# BatteryCharger.net
KiCad netlist of a schematic drawn in Altium Designer
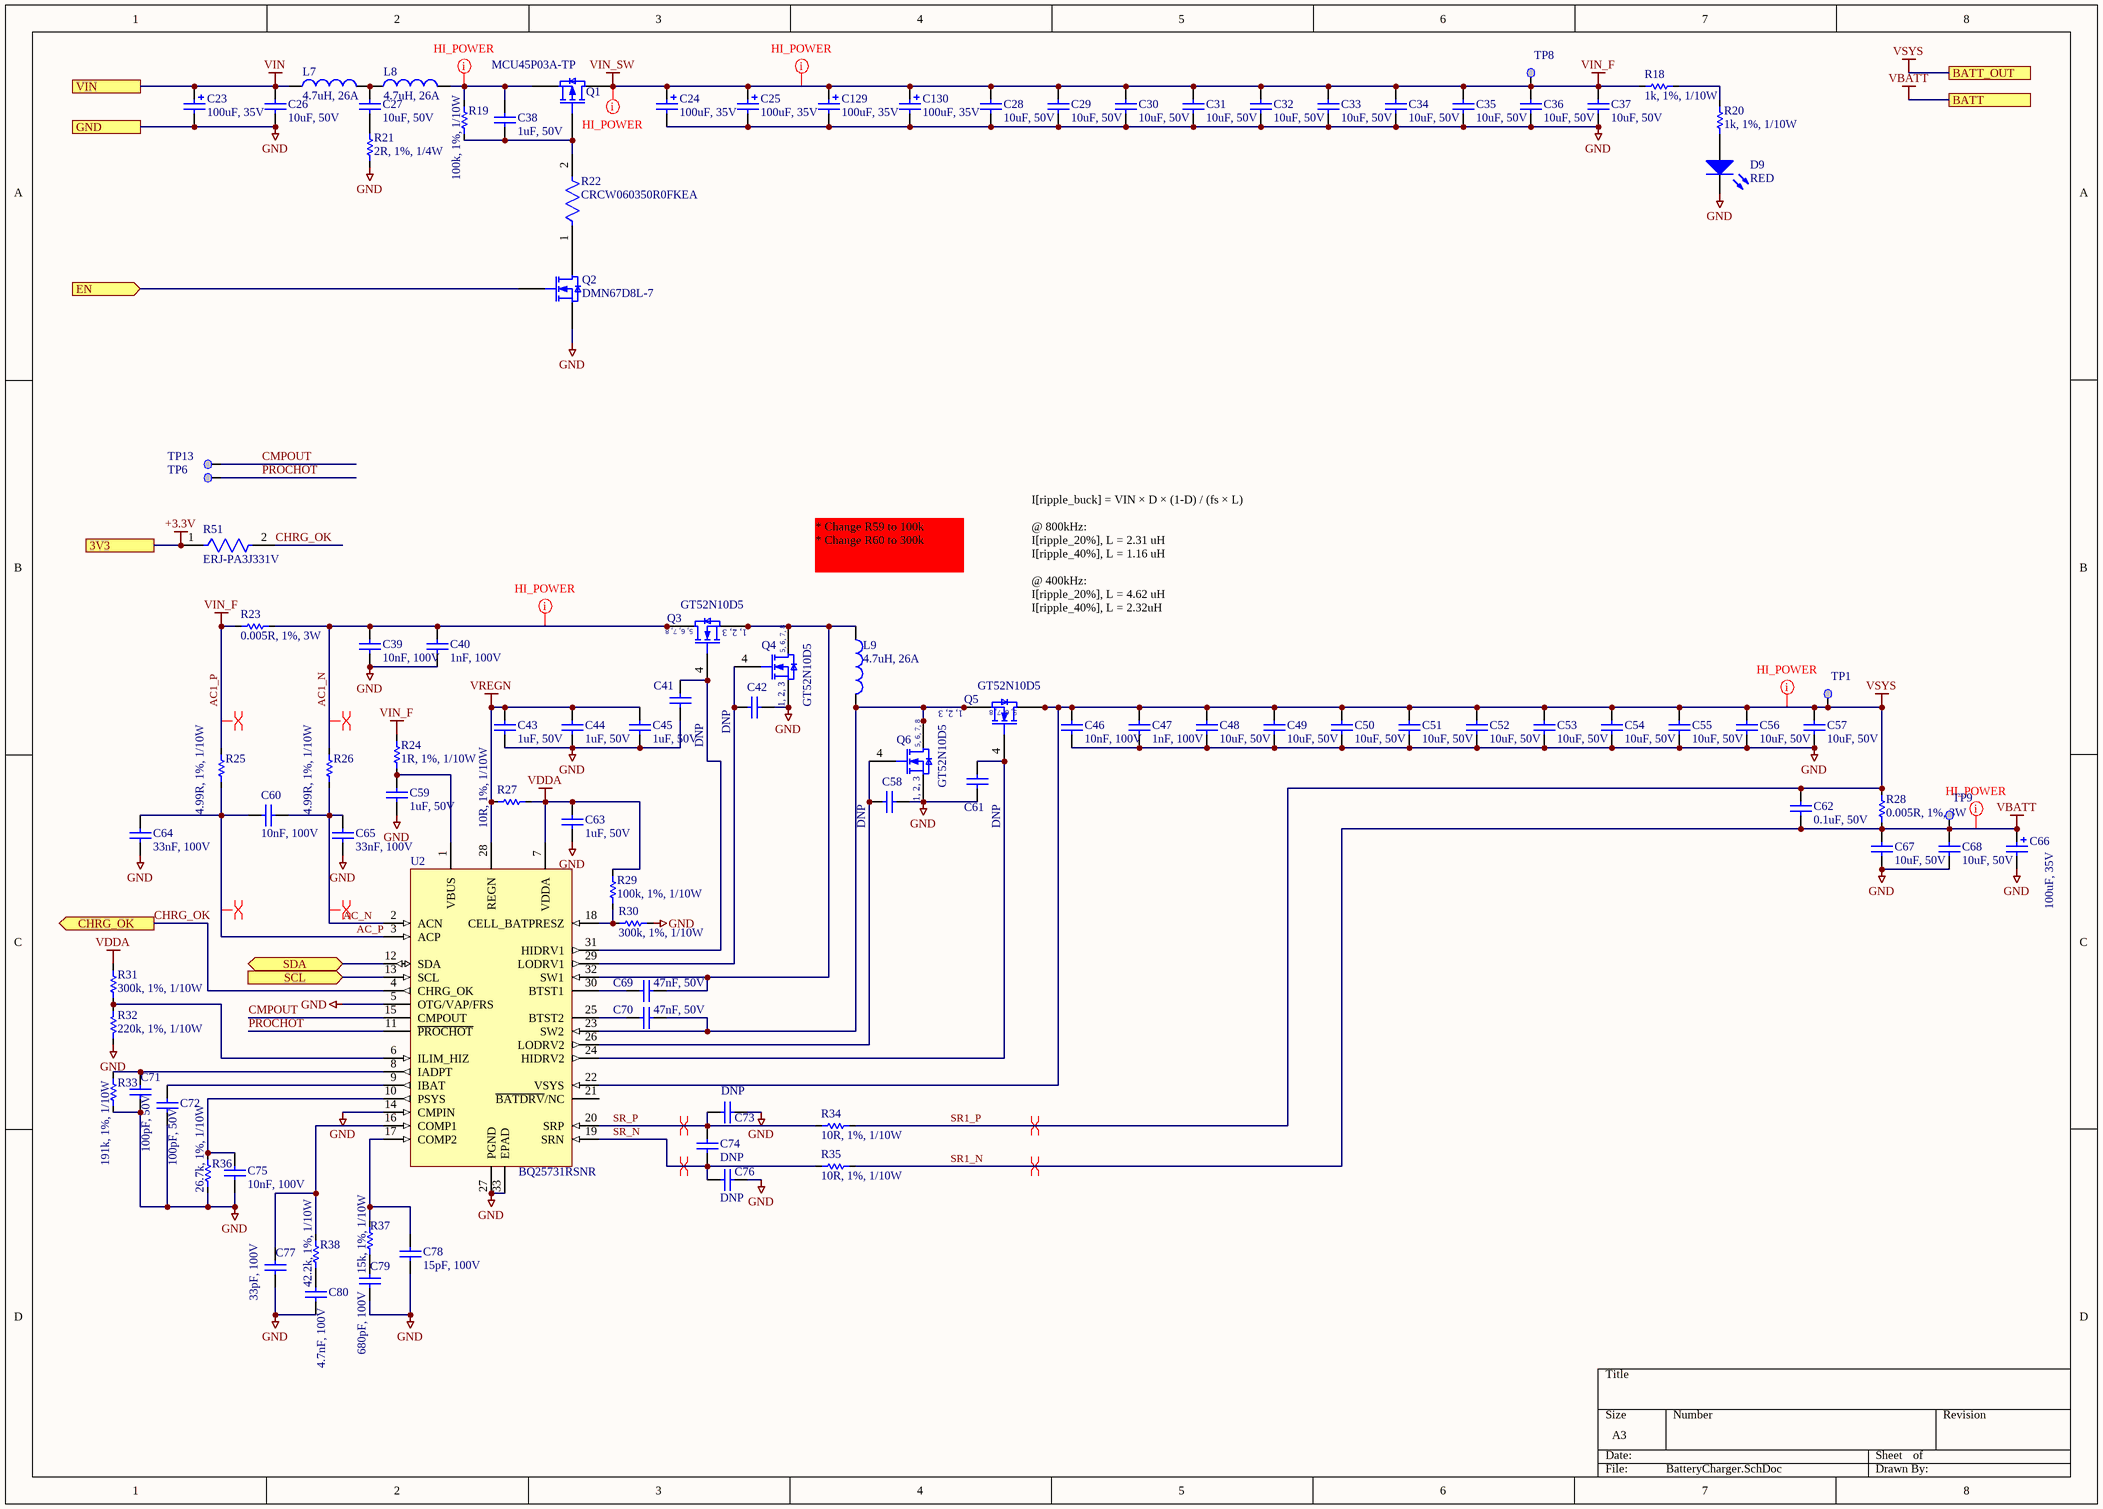
[diagram p0: BatteryCharger.SchDoc]

(export (version "E")
  (design (tool "Eeschema 10.0.6"))
  (components
    (comp (ref "C23")
      (value "100uF, 35V")
      (footprint "CAPAE7866X80L")
      (description "CAP ALUM 100UF 20% 35V SMD")
      (fields (field (name "PART NUMBER") "NS00911"))
      (libsource (lib "FullPartsDB") (part "CAP_POL"))
    )
    (comp (ref "C24")
      (value "100uF, 35V")
      (footprint "CAPAE7866X80L")
      (description "CAP ALUM 100UF 20% 35V SMD")
      (fields (field (name "PART NUMBER") "NS00911"))
      (libsource (lib "FullPartsDB") (part "CAP_POL"))
    )
    (comp (ref "C25")
      (value "100uF, 35V")
      (footprint "CAPAE7866X80L")
      (description "CAP ALUM 100UF 20% 35V SMD")
      (fields (field (name "PART NUMBER") "NS00911"))
      (libsource (lib "FullPartsDB") (part "CAP_POL"))
    )
    (comp (ref "C26")
      (value "10uF, 50V")
      (footprint "1206")
      (description "CAP CER 10UF 50V X7R 1206")
      (fields (field (name "PART NUMBER") "NS00832"))
      (libsource (lib "FullPartsDB") (part "Cap"))
    )
    (comp (ref "C27")
      (value "10uF, 50V")
      (footprint "1206")
      (description "CAP CER 10UF 50V X7R 1206")
      (fields (field (name "PART NUMBER") "NS00832"))
      (libsource (lib "FullPartsDB") (part "Cap"))
    )
    (comp (ref "C28")
      (value "10uF, 50V")
      (footprint "1206")
      (description "CAP CER 10UF 50V X7R 1206")
      (fields (field (name "PART NUMBER") "NS00832"))
      (libsource (lib "FullPartsDB") (part "Cap"))
    )
    (comp (ref "C29")
      (value "10uF, 50V")
      (footprint "1206")
      (description "CAP CER 10UF 50V X7R 1206")
      (fields (field (name "PART NUMBER") "NS00832"))
      (libsource (lib "FullPartsDB") (part "Cap"))
    )
    (comp (ref "C30")
      (value "10uF, 50V")
      (footprint "1206")
      (description "CAP CER 10UF 50V X7R 1206")
      (fields (field (name "PART NUMBER") "NS00832"))
      (libsource (lib "FullPartsDB") (part "Cap"))
    )
    (comp (ref "C31")
      (value "10uF, 50V")
      (footprint "1206")
      (description "CAP CER 10UF 50V X7R 1206")
      (fields (field (name "PART NUMBER") "NS00832"))
      (libsource (lib "FullPartsDB") (part "Cap"))
    )
    (comp (ref "C32")
      (value "10uF, 50V")
      (footprint "1206")
      (description "CAP CER 10UF 50V X7R 1206")
      (fields (field (name "PART NUMBER") "NS00832"))
      (libsource (lib "FullPartsDB") (part "Cap"))
    )
    (comp (ref "C33")
      (value "10uF, 50V")
      (footprint "1206")
      (description "CAP CER 10UF 50V X7R 1206")
      (fields (field (name "PART NUMBER") "NS00832"))
      (libsource (lib "FullPartsDB") (part "Cap"))
    )
    (comp (ref "C34")
      (value "10uF, 50V")
      (footprint "1206")
      (description "CAP CER 10UF 50V X7R 1206")
      (fields (field (name "PART NUMBER") "NS00832"))
      (libsource (lib "FullPartsDB") (part "Cap"))
    )
    (comp (ref "C35")
      (value "10uF, 50V")
      (footprint "1206")
      (description "CAP CER 10UF 50V X7R 1206")
      (fields (field (name "PART NUMBER") "NS00832"))
      (libsource (lib "FullPartsDB") (part "Cap"))
    )
    (comp (ref "C36")
      (value "10uF, 50V")
      (footprint "1206")
      (description "CAP CER 10UF 50V X7R 1206")
      (fields (field (name "PART NUMBER") "NS00832"))
      (libsource (lib "FullPartsDB") (part "Cap"))
    )
    (comp (ref "C37")
      (value "10uF, 50V")
      (footprint "1206")
      (description "CAP CER 10UF 50V X7R 1206")
      (fields (field (name "PART NUMBER") "NS00832"))
      (libsource (lib "FullPartsDB") (part "Cap"))
    )
    (comp (ref "C38")
      (value "1uF, 50V")
      (footprint "0805")
      (description "CAP CER 1UF 50V X7R 0805")
      (fields (field (name "PART NUMBER") "NS00871"))
      (libsource (lib "FullPartsDB") (part "Cap"))
    )
    (comp (ref "C39")
      (value "10nF, 100V")
      (footprint "0603")
      (description "CAP CER 10000PF 100V C0G 0603")
      (fields (field (name "PART NUMBER") "NS00848"))
      (libsource (lib "FullPartsDB") (part "Cap"))
    )
    (comp (ref "C40")
      (value "1nF, 100V")
      (footprint "0603")
      (description "CAP CER 1000PF 100V C0G/NP0 0603")
      (fields (field (name "PART NUMBER") "NS00847"))
      (libsource (lib "FullPartsDB") (part "Cap"))
    )
    (comp (ref "C41")
      (value "DNP")
      (footprint "0603")
      (description "CAP CER 100PF 50V C0G/NP0 0603")
      (fields (field (name "PART NUMBER") "NS00840"))
      (libsource (lib "FullPartsDB") (part "Cap"))
    )
    (comp (ref "C42")
      (value "DNP")
      (footprint "0603")
      (description "CAP CER 100PF 50V C0G/NP0 0603")
      (fields (field (name "PART NUMBER") "NS00840"))
      (libsource (lib "FullPartsDB") (part "Cap"))
    )
    (comp (ref "C43")
      (value "1uF, 50V")
      (footprint "0805")
      (description "CAP CER 1UF 50V X7R 0805")
      (fields (field (name "PART NUMBER") "NS00871"))
      (libsource (lib "FullPartsDB") (part "Cap"))
    )
    (comp (ref "C44")
      (value "1uF, 50V")
      (footprint "0805")
      (description "CAP CER 1UF 50V X7R 0805")
      (fields (field (name "PART NUMBER") "NS00871"))
      (libsource (lib "FullPartsDB") (part "Cap"))
    )
    (comp (ref "C45")
      (value "1uF, 50V")
      (footprint "0805")
      (description "CAP CER 1UF 50V X7R 0805")
      (fields (field (name "PART NUMBER") "NS00871"))
      (libsource (lib "FullPartsDB") (part "Cap"))
    )
    (comp (ref "C46")
      (value "10nF, 100V")
      (footprint "0603")
      (description "CAP CER 10000PF 100V C0G 0603")
      (fields (field (name "PART NUMBER") "NS00848"))
      (libsource (lib "FullPartsDB") (part "Cap"))
    )
    (comp (ref "C47")
      (value "1nF, 100V")
      (footprint "0603")
      (description "CAP CER 1000PF 100V C0G/NP0 0603")
      (fields (field (name "PART NUMBER") "NS00847"))
      (libsource (lib "FullPartsDB") (part "Cap"))
    )
    (comp (ref "C48")
      (value "10uF, 50V")
      (footprint "1206")
      (description "CAP CER 10UF 50V X7R 1206")
      (fields (field (name "PART NUMBER") "NS00832"))
      (libsource (lib "FullPartsDB") (part "Cap"))
    )
    (comp (ref "C49")
      (value "10uF, 50V")
      (footprint "1206")
      (description "CAP CER 10UF 50V X7R 1206")
      (fields (field (name "PART NUMBER") "NS00832"))
      (libsource (lib "FullPartsDB") (part "Cap"))
    )
    (comp (ref "C50")
      (value "10uF, 50V")
      (footprint "1206")
      (description "CAP CER 10UF 50V X7R 1206")
      (fields (field (name "PART NUMBER") "NS00832"))
      (libsource (lib "FullPartsDB") (part "Cap"))
    )
    (comp (ref "C51")
      (value "10uF, 50V")
      (footprint "1206")
      (description "CAP CER 10UF 50V X7R 1206")
      (fields (field (name "PART NUMBER") "NS00832"))
      (libsource (lib "FullPartsDB") (part "Cap"))
    )
    (comp (ref "C52")
      (value "10uF, 50V")
      (footprint "1206")
      (description "CAP CER 10UF 50V X7R 1206")
      (fields (field (name "PART NUMBER") "NS00832"))
      (libsource (lib "FullPartsDB") (part "Cap"))
    )
    (comp (ref "C53")
      (value "10uF, 50V")
      (footprint "1206")
      (description "CAP CER 10UF 50V X7R 1206")
      (fields (field (name "PART NUMBER") "NS00832"))
      (libsource (lib "FullPartsDB") (part "Cap"))
    )
    (comp (ref "C54")
      (value "10uF, 50V")
      (footprint "1206")
      (description "CAP CER 10UF 50V X7R 1206")
      (fields (field (name "PART NUMBER") "NS00832"))
      (libsource (lib "FullPartsDB") (part "Cap"))
    )
    (comp (ref "C55")
      (value "10uF, 50V")
      (footprint "1206")
      (description "CAP CER 10UF 50V X7R 1206")
      (fields (field (name "PART NUMBER") "NS00832"))
      (libsource (lib "FullPartsDB") (part "Cap"))
    )
    (comp (ref "C56")
      (value "10uF, 50V")
      (footprint "1206")
      (description "CAP CER 10UF 50V X7R 1206")
      (fields (field (name "PART NUMBER") "NS00832"))
      (libsource (lib "FullPartsDB") (part "Cap"))
    )
    (comp (ref "C57")
      (value "10uF, 50V")
      (footprint "1206")
      (description "CAP CER 10UF 50V X7R 1206")
      (fields (field (name "PART NUMBER") "NS00832"))
      (libsource (lib "FullPartsDB") (part "Cap"))
    )
    (comp (ref "C58")
      (value "DNP")
      (footprint "0603")
      (description "CAP CER 100PF 50V C0G/NP0 0603")
      (fields (field (name "PART NUMBER") "NS00840"))
      (libsource (lib "FullPartsDB") (part "Cap"))
    )
    (comp (ref "C59")
      (value "1uF, 50V")
      (footprint "0805")
      (description "CAP CER 1UF 50V X7R 0805")
      (fields (field (name "PART NUMBER") "NS00871"))
      (libsource (lib "FullPartsDB") (part "Cap"))
    )
    (comp (ref "C60")
      (value "10nF, 100V")
      (footprint "0603")
      (description "CAP CER 10000PF 100V C0G 0603")
      (fields (field (name "PART NUMBER") "NS00848"))
      (libsource (lib "FullPartsDB") (part "Cap"))
    )
    (comp (ref "C61")
      (value "DNP")
      (footprint "0603")
      (description "CAP CER 100PF 50V C0G/NP0 0603")
      (fields (field (name "PART NUMBER") "NS00840"))
      (libsource (lib "FullPartsDB") (part "Cap"))
    )
    (comp (ref "C62")
      (value "0.1uF, 50V")
      (footprint "0603")
      (description "CAP CER 0.1UF 50V X7R 0603")
      (fields (field (name "PART NUMBER") "NS00838"))
      (libsource (lib "FullPartsDB") (part "Cap"))
    )
    (comp (ref "C63")
      (value "1uF, 50V")
      (footprint "0805")
      (description "CAP CER 1UF 50V X7R 0805")
      (fields (field (name "PART NUMBER") "NS00871"))
      (libsource (lib "FullPartsDB") (part "Cap"))
    )
    (comp (ref "C64")
      (value "33nF, 100V")
      (footprint "0805_CAP")
      (description "CAP CER 0.033UF 100V C0G 0805")
      (fields (field (name "PART NUMBER") "NS00800"))
      (libsource (lib "FullPartsDB") (part "Cap"))
    )
    (comp (ref "C65")
      (value "33nF, 100V")
      (footprint "0805_CAP")
      (description "CAP CER 0.033UF 100V C0G 0805")
      (fields (field (name "PART NUMBER") "NS00800"))
      (libsource (lib "FullPartsDB") (part "Cap"))
    )
    (comp (ref "C66")
      (value "100uF, 35V")
      (footprint "CAPAE7866X80L")
      (description "CAP ALUM 100UF 20% 35V SMD")
      (fields (field (name "PART NUMBER") "NS00911"))
      (libsource (lib "FullPartsDB") (part "CAP_POL"))
    )
    (comp (ref "C67")
      (value "10uF, 50V")
      (footprint "1206")
      (description "CAP CER 10UF 50V X7R 1206")
      (fields (field (name "PART NUMBER") "NS00832"))
      (libsource (lib "FullPartsDB") (part "Cap"))
    )
    (comp (ref "C68")
      (value "10uF, 50V")
      (footprint "1206")
      (description "CAP CER 10UF 50V X7R 1206")
      (fields (field (name "PART NUMBER") "NS00832"))
      (libsource (lib "FullPartsDB") (part "Cap"))
    )
    (comp (ref "C69")
      (value "47nF, 50V")
      (footprint "0603")
      (description "CAP CER 0.047UF 50V X7R 0603")
      (fields (field (name "PART NUMBER") "NS00804"))
      (libsource (lib "FullPartsDB") (part "Cap"))
    )
    (comp (ref "C70")
      (value "47nF, 50V")
      (footprint "0603")
      (description "CAP CER 0.047UF 50V X7R 0603")
      (fields (field (name "PART NUMBER") "NS00804"))
      (libsource (lib "FullPartsDB") (part "Cap"))
    )
    (comp (ref "C71")
      (value "100pF, 50V")
      (footprint "0603")
      (description "CAP CER 100PF 50V C0G/NP0 0603")
      (fields (field (name "PART NUMBER") "NS00840"))
      (libsource (lib "FullPartsDB") (part "Cap"))
    )
    (comp (ref "C72")
      (value "100pF, 50V")
      (footprint "0603")
      (description "CAP CER 100PF 50V C0G/NP0 0603")
      (fields (field (name "PART NUMBER") "NS00840"))
      (libsource (lib "FullPartsDB") (part "Cap"))
    )
    (comp (ref "C73")
      (value "DNP")
      (footprint "0603")
      (description "CAP CER 0.068UF 50V X7R 0603")
      (fields (field (name "PART NUMBER") "NS00895"))
      (libsource (lib "FullPartsDB") (part "Cap"))
    )
    (comp (ref "C74")
      (value "DNP")
      (footprint "0603")
      (description "CAP CER 0.068UF 50V X7R 0603")
      (fields (field (name "PART NUMBER") "NS00895"))
      (libsource (lib "FullPartsDB") (part "Cap"))
    )
    (comp (ref "C75")
      (value "10nF, 100V")
      (footprint "0603")
      (description "CAP CER 10000PF 100V C0G 0603")
      (fields (field (name "PART NUMBER") "NS00848"))
      (libsource (lib "FullPartsDB") (part "Cap"))
    )
    (comp (ref "C76")
      (value "DNP")
      (footprint "0603")
      (description "CAP CER 0.068UF 50V X7R 0603")
      (fields (field (name "PART NUMBER") "NS00895"))
      (libsource (lib "FullPartsDB") (part "Cap"))
    )
    (comp (ref "C77")
      (value "33pF, 100V")
      (footprint "0603")
      (description "CAP CER 33PF 100V C0G/NP0 0603")
      (fields (field (name "PART NUMBER") "NS00931"))
      (libsource (lib "FullPartsDB") (part "Cap"))
    )
    (comp (ref "C78")
      (value "15pF, 100V")
      (footprint "0603")
      (description "CAP CER 15PF 100V C0G/NP0 0603")
      (fields (field (name "PART NUMBER") "NS00932"))
      (libsource (lib "FullPartsDB") (part "Cap"))
    )
    (comp (ref "C79")
      (value "680pF, 100V")
      (footprint "0603")
      (description "CAP CER 680PF 100V C0G 0603")
      (fields (field (name "PART NUMBER") "NS00933"))
      (libsource (lib "FullPartsDB") (part "Cap"))
    )
    (comp (ref "C80")
      (value "4.7nF, 100V")
      (footprint "0603")
      (description "CAP CER 4700PF 100V C0G 0603")
      (fields (field (name "PART NUMBER") "NS00930"))
      (libsource (lib "FullPartsDB") (part "Cap"))
    )
    (comp (ref "C129")
      (value "100uF, 35V")
      (footprint "CAPAE7866X80L")
      (description "CAP ALUM 100UF 20% 35V SMD")
      (fields (field (name "PART NUMBER") "NS00911"))
      (libsource (lib "FullPartsDB") (part "CAP_POL"))
    )
    (comp (ref "C130")
      (value "100uF, 35V")
      (footprint "CAPAE7866X80L")
      (description "CAP ALUM 100UF 20% 35V SMD")
      (fields (field (name "PART NUMBER") "NS00911"))
      (libsource (lib "FullPartsDB") (part "CAP_POL"))
    )
    (comp (ref "D9")
      (value "RED")
      (footprint "0603_DIODE_K1A2")
      (description "LED RED CLEAR 1608 SMD")
      (fields (field (name "PART NUMBER") "NS00945"))
      (libsource (lib "FullPartsDB") (part "LED_K1A2"))
    )
    (comp (ref "L7")
      (value "4.7uH, 26A")
      (footprint "INDM178169X70N")
      (description "FIXED IND 4.7UH 26A 5.5 MOHM SMD")
      (fields (field (name "PART NUMBER") "NS00854"))
      (libsource (lib "FullPartsDB") (part "Inductor"))
    )
    (comp (ref "L8")
      (value "4.7uH, 26A")
      (footprint "INDM178169X70N")
      (description "FIXED IND 4.7UH 26A 5.5 MOHM SMD")
      (fields (field (name "PART NUMBER") "NS00854"))
      (libsource (lib "FullPartsDB") (part "Inductor"))
    )
    (comp (ref "L9")
      (value "4.7uH, 26A")
      (footprint "INDM178169X70N")
      (description "FIXED IND 4.7UH 26A 5.5 MOHM SMD")
      (fields (field (name "PART NUMBER") "NS00854"))
      (libsource (lib "FullPartsDB") (part "Inductor"))
    )
    (comp (ref "Q1")
      (value "MCU45P03A-TP")
      (footprint "DPAK")
      (description "P-CHANNEL MOSFET, DPAK")
      (fields (field (name "PART NUMBER") "NS00810"))
      (libsource (lib "FullPartsDB") (part "FET_P_GDS"))
    )
    (comp (ref "Q2")
      (value "DMN67D8L-7")
      (footprint "SOT23-3")
      (description "MOSFET N-CH 60V 210MA SOT23")
      (fields (field (name "PART NUMBER") "NS00873") (field (name "PUBLISHER") "Altium Limited"))
      (libsource (lib "FullPartsDB") (part "FET_N_GSD"))
    )
    (comp (ref "Q3")
      (value "GT52N10D5")
      (footprint "8-PowerSMD")
      (description "N-CH MOSFET 100V 71A 8-PowerTDFN")
      (fields (field (name "PART NUMBER") "NS00856") (field (name "PUBLISHER") "Altium Limited"))
      (libsource (lib "FullPartsDB") (part "FET_N_1G3S4D"))
    )
    (comp (ref "Q4")
      (value "GT52N10D5")
      (footprint "8-PowerSMD")
      (description "N-CH MOSFET 100V 71A 8-PowerTDFN")
      (fields (field (name "PART NUMBER") "NS00856") (field (name "PUBLISHER") "Altium Limited"))
      (libsource (lib "FullPartsDB") (part "FET_N_1G3S4D"))
    )
    (comp (ref "Q5")
      (value "GT52N10D5")
      (footprint "8-PowerSMD")
      (description "N-CH MOSFET 100V 71A 8-PowerTDFN")
      (fields (field (name "PART NUMBER") "NS00856") (field (name "PUBLISHER") "Altium Limited"))
      (libsource (lib "FullPartsDB") (part "FET_N_1G3S4D"))
    )
    (comp (ref "Q6")
      (value "GT52N10D5")
      (footprint "8-PowerSMD")
      (description "N-CH MOSFET 100V 71A 8-PowerTDFN")
      (fields (field (name "PART NUMBER") "NS00856") (field (name "PUBLISHER") "Altium Limited"))
      (libsource (lib "FullPartsDB") (part "FET_N_1G3S4D"))
    )
    (comp (ref "R18")
      (value "1k, 1%, 1/10W")
      (footprint "0603")
      (description "RES 1K OHM 1% 1/10W 0603")
      (fields (field (name "PART NUMBER") "NS00882"))
      (libsource (lib "FullPartsDB") (part "RESISTOR"))
    )
    (comp (ref "R19")
      (value "100k, 1%, 1/10W")
      (footprint "0603")
      (description "RES 100K OHM 1% 1/10W 0603")
      (fields (field (name "PART NUMBER") "NS00835"))
      (libsource (lib "FullPartsDB") (part "RESISTOR"))
    )
    (comp (ref "R20")
      (value "1k, 1%, 1/10W")
      (footprint "0603")
      (description "RES 1K OHM 1% 1/10W 0603")
      (fields (field (name "PART NUMBER") "NS00882"))
      (libsource (lib "FullPartsDB") (part "RESISTOR"))
    )
    (comp (ref "R21")
      (value "2R, 1%, 1/4W")
      (footprint "1206")
      (description "RES 2 OHM 1% 1/4W 1206")
      (fields (field (name "PART NUMBER") "NS00946"))
      (libsource (lib "FullPartsDB") (part "RESISTOR"))
    )
    (comp (ref "R22")
      (value "CRCW060350R0FKEA")
      (footprint "FP-CRCW0603-e3-IPC_A")
      (description "RES Thick Film, 50Ω, 1%, 0.1W, 100ppm/°C, 0603")
      (fields (field (name "TOLERANCE") "1%"))
      (libsource (lib "Altium Content Vault") (part "1029c3af85768c4190bb7ad29bc67b5"))
    )
    (comp (ref "R23")
      (value "0.005R, 1%, 3W")
      (footprint "2512_RES_1")
      (description "RES 0.005 OHM 1% 3W 2512")
      (fields (field (name "PART NUMBER") "NS00798"))
      (libsource (lib "FullPartsDB") (part "RESISTOR"))
    )
    (comp (ref "R24")
      (value "1R, 1%, 1/10W")
      (footprint "0603")
      (description "RES 1 OHM 1% 1/10W 0603")
      (fields (field (name "PART NUMBER") "NS00811"))
      (libsource (lib "FullPartsDB") (part "RESISTOR"))
    )
    (comp (ref "R25")
      (value "4.99R, 1%, 1/10W")
      (footprint "0603")
      (description "RES 4.99 OHM 1% 1/10W 0603")
      (fields (field (name "PART NUMBER") "NS00799"))
      (libsource (lib "FullPartsDB") (part "RESISTOR"))
    )
    (comp (ref "R26")
      (value "4.99R, 1%, 1/10W")
      (footprint "0603")
      (description "RES 4.99 OHM 1% 1/10W 0603")
      (fields (field (name "PART NUMBER") "NS00799"))
      (libsource (lib "FullPartsDB") (part "RESISTOR"))
    )
    (comp (ref "R27")
      (value "10R, 1%, 1/10W")
      (footprint "0603")
      (description "RES 10 OHM 1% 1/10W 0603")
      (fields (field (name "PART NUMBER") "NS00796"))
      (libsource (lib "FullPartsDB") (part "RESISTOR"))
    )
    (comp (ref "R28")
      (value "0.005R, 1%, 3W")
      (footprint "2512_RES_1")
      (description "RES 0.005 OHM 1% 3W 2512")
      (fields (field (name "PART NUMBER") "NS00798"))
      (libsource (lib "FullPartsDB") (part "RESISTOR"))
    )
    (comp (ref "R29")
      (value "100k, 1%, 1/10W")
      (footprint "0603")
      (description "RES 100K OHM 1% 1/10W 0603")
      (fields (field (name "PART NUMBER") "NS00835"))
      (libsource (lib "FullPartsDB") (part "RESISTOR"))
    )
    (comp (ref "R30")
      (value "300k, 1%, 1/10W")
      (footprint "0603")
      (description "RES 300K OHM 1% 1/10W 0603")
      (fields (field (name "PART NUMBER") "NS00837"))
      (libsource (lib "FullPartsDB") (part "RESISTOR"))
    )
    (comp (ref "R31")
      (value "300k, 1%, 1/10W")
      (footprint "0603")
      (description "RES 300K OHM 1% 1/10W 0603")
      (fields (field (name "PART NUMBER") "NS00837"))
      (libsource (lib "FullPartsDB") (part "RESISTOR"))
    )
    (comp (ref "R32")
      (value "220k, 1%, 1/10W")
      (footprint "0603")
      (description "RES SMD 220K OHM 1% 1/10W 0603")
      (fields (field (name "PART NUMBER") "NS00915"))
      (libsource (lib "FullPartsDB") (part "RESISTOR"))
    )
    (comp (ref "R33")
      (value "191k, 1%, 1/10W")
      (footprint "0603")
      (description "RES 191K OHM 1% 1/10W 0603")
      (fields (field (name "PART NUMBER") "NS00821"))
      (libsource (lib "FullPartsDB") (part "RESISTOR"))
    )
    (comp (ref "R34")
      (value "10R, 1%, 1/10W")
      (footprint "0603")
      (description "RES 10 OHM 1% 1/10W 0603")
      (fields (field (name "PART NUMBER") "NS00796"))
      (libsource (lib "FullPartsDB") (part "RESISTOR"))
    )
    (comp (ref "R35")
      (value "10R, 1%, 1/10W")
      (footprint "0603")
      (description "RES 10 OHM 1% 1/10W 0603")
      (fields (field (name "PART NUMBER") "NS00796"))
      (libsource (lib "FullPartsDB") (part "RESISTOR"))
    )
    (comp (ref "R36")
      (value "26.7k, 1%, 1/10W")
      (footprint "0603")
      (description "RES 26.7K OHM 1% 1/10W 0603")
      (fields (field (name "PART NUMBER") "NS00823"))
      (libsource (lib "FullPartsDB") (part "RESISTOR"))
    )
    (comp (ref "R37")
      (value "15k, 1%, 1/10W")
      (footprint "0603")
      (description "RES 15K OHM 1% 1/10W 0603")
      (fields (field (name "PART NUMBER") "NS00834"))
      (libsource (lib "FullPartsDB") (part "RESISTOR"))
    )
    (comp (ref "R38")
      (value "42.2k, 1%, 1/10W")
      (footprint "0603")
      (description "RES 42.2K OHM 1% 1/10W 0603")
      (fields (field (name "PART NUMBER") "NS00822"))
      (libsource (lib "FullPartsDB") (part "RESISTOR"))
    )
    (comp (ref "R51")
      (value "ERJ-PA3J331V")
      (footprint "FP-ERJPA3-MFG")
      (description "RES SMD 330 OHM 5% 1/4W 0603")
      (fields (field (name "TOLERANCE") "5%"))
      (libsource (lib "Altium Content Vault") (part "1029c3af85768c4190bb7ad29bc67b5"))
    )
    (comp (ref "TP1")
      (value "Test Point")
      (footprint "TEST POINT 40 Mil")
      (description "Test Point 0.3mm")
      (libsource (lib "1_EverythingElse") (part "Test Point"))
    )
    (comp (ref "TP6")
      (value "Test Point")
      (footprint "TEST POINT 40 Mil")
      (description "Test Point 0.3mm")
      (libsource (lib "") (part "Test Point_1"))
    )
    (comp (ref "TP8")
      (value "Test Point")
      (footprint "TEST POINT 40 Mil")
      (description "Test Point 0.3mm")
      (libsource (lib "1_EverythingElse") (part "Test Point"))
    )
    (comp (ref "TP9")
      (value "Test Point")
      (footprint "TEST POINT 40 Mil")
      (description "Test Point 0.3mm")
      (libsource (lib "1_EverythingElse") (part "Test Point"))
    )
    (comp (ref "TP13")
      (value "Test Point")
      (footprint "TEST POINT 40 Mil")
      (description "Test Point 0.3mm")
      (libsource (lib "") (part "Test Point_1"))
    )
    (comp (ref "U2")
      (value "BQ25731RSNR")
      (footprint "QFN40P400X400X80_HS-33L")
      (description "I2C 1-5 CELL NVDC BUCK-BOOST BAT")
      (fields (field (name "PART NUMBER") "NS00795"))
      (libsource (lib "FullPartsDB") (part "TI_BQ257[2.3]X"))
    )
  )
  (nets
    (net (code "1") (name "+3.3V") (class "Default")
      (node (ref "R51") (pin "1") (pinfunction "1_1") (pintype "passive"))
    )
    (net (code "2") (name "/AC1_N") (class "Default")
      (node (ref "C39") (pin "2") (pinfunction "2_2") (pintype "passive"))
      (node (ref "C40") (pin "2") (pinfunction "2_2") (pintype "passive"))
      (node (ref "Q3") (pin "5") (pinfunction "D1_5") (pintype "passive"))
      (node (ref "Q3") (pin "6") (pinfunction "D2_6") (pintype "passive"))
      (node (ref "Q3") (pin "7") (pinfunction "D3_7") (pintype "passive"))
      (node (ref "Q3") (pin "8") (pinfunction "D4_8") (pintype "passive"))
      (node (ref "R23") (pin "2") (pinfunction "2_2") (pintype "passive"))
      (node (ref "R26") (pin "2") (pinfunction "2_2") (pintype "passive"))
    )
    (net (code "3") (name "/AC_N") (class "Default")
      (node (ref "C60") (pin "1") (pinfunction "1_1") (pintype "passive"))
      (node (ref "C65") (pin "2") (pinfunction "2_2") (pintype "passive"))
      (node (ref "R26") (pin "1") (pinfunction "1_1") (pintype "passive"))
      (node (ref "U2") (pin "2") (pinfunction "ACN_2") (pintype "input"))
    )
    (net (code "4") (name "/AC_P") (class "Default")
      (node (ref "C60") (pin "2") (pinfunction "2_2") (pintype "passive"))
      (node (ref "C64") (pin "2") (pinfunction "2_2") (pintype "passive"))
      (node (ref "R25") (pin "1") (pinfunction "1_1") (pintype "passive"))
      (node (ref "U2") (pin "3") (pinfunction "ACP_3") (pintype "input"))
    )
    (net (code "5") (name "/CHRG_OK") (class "Default")
      (node (ref "R51") (pin "2") (pinfunction "2_2") (pintype "passive"))
      (node (ref "U2") (pin "4") (pinfunction "CHRG_OK_4") (pintype "output"))
    )
    (net (code "6") (name "/CMPOUT") (class "Default")
      (node (ref "TP13") (pin "1") (pinfunction "1_1") (pintype "passive"))
      (node (ref "U2") (pin "15") (pinfunction "CMPOUT_15") (pintype "open_collector"))
    )
    (net (code "7") (name "/EN") (class "Default")
      (node (ref "Q2") (pin "1") (pinfunction "G_1") (pintype "passive"))
    )
    (net (code "8") (name "/PROCHOT") (class "Default")
      (node (ref "TP6") (pin "1") (pinfunction "1_1") (pintype "passive"))
      (node (ref "U2") (pin "11") (pinfunction "PROCHOT_11") (pintype "open_collector"))
    )
    (net (code "9") (name "/SCL") (class "Default")
      (node (ref "U2") (pin "13") (pinfunction "SCL_13") (pintype "input"))
    )
    (net (code "10") (name "/SDA") (class "Default")
      (node (ref "U2") (pin "12") (pinfunction "SDA_12") (pintype "bidirectional"))
    )
    (net (code "11") (name "/SR_N") (class "Default")
      (node (ref "C74") (pin "1") (pinfunction "1_1") (pintype "passive"))
      (node (ref "C76") (pin "1") (pinfunction "1_1") (pintype "passive"))
      (node (ref "R35") (pin "1") (pinfunction "1_1") (pintype "passive"))
      (node (ref "U2") (pin "19") (pinfunction "SRN_19") (pintype "input"))
    )
    (net (code "12") (name "/SR_P") (class "Default")
      (node (ref "C73") (pin "1") (pinfunction "1_1") (pintype "passive"))
      (node (ref "C74") (pin "2") (pinfunction "2_2") (pintype "passive"))
      (node (ref "R34") (pin "1") (pinfunction "1_1") (pintype "passive"))
      (node (ref "U2") (pin "20") (pinfunction "SRP_20") (pintype "input"))
    )
    (net (code "13") (name "GND") (class "Default")
      (node (ref "C129") (pin "2") (pinfunction "2_2") (pintype "passive"))
      (node (ref "C130") (pin "2") (pinfunction "2_2") (pintype "passive"))
      (node (ref "C23") (pin "2") (pinfunction "2_2") (pintype "passive"))
      (node (ref "C24") (pin "2") (pinfunction "2_2") (pintype "passive"))
      (node (ref "C25") (pin "2") (pinfunction "2_2") (pintype "passive"))
      (node (ref "C26") (pin "1") (pinfunction "1_1") (pintype "passive"))
      (node (ref "C28") (pin "1") (pinfunction "1_1") (pintype "passive"))
      (node (ref "C29") (pin "1") (pinfunction "1_1") (pintype "passive"))
      (node (ref "C30") (pin "1") (pinfunction "1_1") (pintype "passive"))
      (node (ref "C31") (pin "1") (pinfunction "1_1") (pintype "passive"))
      (node (ref "C32") (pin "1") (pinfunction "1_1") (pintype "passive"))
      (node (ref "C33") (pin "1") (pinfunction "1_1") (pintype "passive"))
      (node (ref "C34") (pin "1") (pinfunction "1_1") (pintype "passive"))
      (node (ref "C35") (pin "1") (pinfunction "1_1") (pintype "passive"))
      (node (ref "C36") (pin "1") (pinfunction "1_1") (pintype "passive"))
      (node (ref "C37") (pin "1") (pinfunction "1_1") (pintype "passive"))
      (node (ref "C39") (pin "1") (pinfunction "1_1") (pintype "passive"))
      (node (ref "C40") (pin "1") (pinfunction "1_1") (pintype "passive"))
      (node (ref "C41") (pin "2") (pinfunction "2_2") (pintype "passive"))
      (node (ref "C42") (pin "2") (pinfunction "2_2") (pintype "passive"))
      (node (ref "C43") (pin "1") (pinfunction "1_1") (pintype "passive"))
      (node (ref "C44") (pin "1") (pinfunction "1_1") (pintype "passive"))
      (node (ref "C45") (pin "1") (pinfunction "1_1") (pintype "passive"))
      (node (ref "C46") (pin "1") (pinfunction "1_1") (pintype "passive"))
      (node (ref "C47") (pin "1") (pinfunction "1_1") (pintype "passive"))
      (node (ref "C48") (pin "1") (pinfunction "1_1") (pintype "passive"))
      (node (ref "C49") (pin "1") (pinfunction "1_1") (pintype "passive"))
      (node (ref "C50") (pin "1") (pinfunction "1_1") (pintype "passive"))
      (node (ref "C51") (pin "1") (pinfunction "1_1") (pintype "passive"))
      (node (ref "C52") (pin "1") (pinfunction "1_1") (pintype "passive"))
      (node (ref "C53") (pin "1") (pinfunction "1_1") (pintype "passive"))
      (node (ref "C54") (pin "1") (pinfunction "1_1") (pintype "passive"))
      (node (ref "C55") (pin "1") (pinfunction "1_1") (pintype "passive"))
      (node (ref "C56") (pin "1") (pinfunction "1_1") (pintype "passive"))
      (node (ref "C57") (pin "1") (pinfunction "1_1") (pintype "passive"))
      (node (ref "C58") (pin "2") (pinfunction "2_2") (pintype "passive"))
      (node (ref "C59") (pin "1") (pinfunction "1_1") (pintype "passive"))
      (node (ref "C61") (pin "2") (pinfunction "2_2") (pintype "passive"))
      (node (ref "C63") (pin "1") (pinfunction "1_1") (pintype "passive"))
      (node (ref "C64") (pin "1") (pinfunction "1_1") (pintype "passive"))
      (node (ref "C65") (pin "1") (pinfunction "1_1") (pintype "passive"))
      (node (ref "C66") (pin "2") (pinfunction "2_2") (pintype "passive"))
      (node (ref "C67") (pin "1") (pinfunction "1_1") (pintype "passive"))
      (node (ref "C68") (pin "1") (pinfunction "1_1") (pintype "passive"))
      (node (ref "C71") (pin "2") (pinfunction "2_2") (pintype "passive"))
      (node (ref "C72") (pin "1") (pinfunction "1_1") (pintype "passive"))
      (node (ref "C73") (pin "2") (pinfunction "2_2") (pintype "passive"))
      (node (ref "C75") (pin "1") (pinfunction "1_1") (pintype "passive"))
      (node (ref "C76") (pin "2") (pinfunction "2_2") (pintype "passive"))
      (node (ref "C77") (pin "1") (pinfunction "1_1") (pintype "passive"))
      (node (ref "C78") (pin "1") (pinfunction "1_1") (pintype "passive"))
      (node (ref "C79") (pin "1") (pinfunction "1_1") (pintype "passive"))
      (node (ref "C80") (pin "1") (pinfunction "1_1") (pintype "passive"))
      (node (ref "D9") (pin "2") (pinfunction "K_2") (pintype "passive"))
      (node (ref "Q2") (pin "2") (pinfunction "S_2") (pintype "passive"))
      (node (ref "Q4") (pin "1") (pinfunction "S1_1") (pintype "passive"))
      (node (ref "Q4") (pin "2") (pinfunction "S2_2") (pintype "passive"))
      (node (ref "Q4") (pin "3") (pinfunction "S3_3") (pintype "passive"))
      (node (ref "Q6") (pin "1") (pinfunction "S1_1") (pintype "passive"))
      (node (ref "Q6") (pin "2") (pinfunction "S2_2") (pintype "passive"))
      (node (ref "Q6") (pin "3") (pinfunction "S3_3") (pintype "passive"))
      (node (ref "R21") (pin "1") (pinfunction "1_1") (pintype "passive"))
      (node (ref "R30") (pin "1") (pinfunction "1_1") (pintype "passive"))
      (node (ref "R32") (pin "2") (pinfunction "2_2") (pintype "passive"))
      (node (ref "R33") (pin "1") (pinfunction "1_1") (pintype "passive"))
      (node (ref "R36") (pin "1") (pinfunction "1_1") (pintype "passive"))
      (node (ref "U2") (pin "14") (pinfunction "CMPIN_14") (pintype "input"))
      (node (ref "U2") (pin "27") (pinfunction "PGND_27") (pintype "power_in"))
      (node (ref "U2") (pin "33") (pinfunction "EPAD_33") (pintype "power_in"))
      (node (ref "U2") (pin "5") (pinfunction "OTG/VAP/FRS_5") (pintype "passive"))
    )
    (net (code "14") (name "Net-(C27-Pad1)") (class "Default")
      (node (ref "C27") (pin "1") (pinfunction "1_1") (pintype "passive"))
      (node (ref "R21") (pin "2") (pinfunction "2_2") (pintype "passive"))
    )
    (net (code "15") (name "Net-(C27-Pad2)") (class "Default")
      (node (ref "C27") (pin "2") (pinfunction "2_2") (pintype "passive"))
      (node (ref "L7") (pin "2") (pinfunction "2_2") (pintype "passive"))
      (node (ref "L8") (pin "1") (pinfunction "1_1") (pintype "passive"))
    )
    (net (code "16") (name "Net-(C79-Pad2)") (class "Default")
      (node (ref "C79") (pin "2") (pinfunction "2_2") (pintype "passive"))
      (node (ref "R37") (pin "1") (pinfunction "1_1") (pintype "passive"))
    )
    (net (code "17") (name "Net-(C80-Pad2)") (class "Default")
      (node (ref "C80") (pin "2") (pinfunction "2_2") (pintype "passive"))
      (node (ref "R38") (pin "1") (pinfunction "1_1") (pintype "passive"))
    )
    (net (code "18") (name "Net-(D9-A)") (class "Default")
      (node (ref "D9") (pin "1") (pinfunction "A_1") (pintype "passive"))
      (node (ref "R20") (pin "2") (pinfunction "2_2") (pintype "passive"))
    )
    (net (code "19") (name "Net-(Q1-G)") (class "Default")
      (node (ref "C38") (pin "1") (pinfunction "1_1") (pintype "passive"))
      (node (ref "Q1") (pin "1") (pinfunction "G_1") (pintype "passive"))
      (node (ref "R19") (pin "1") (pinfunction "1_1") (pintype "passive"))
      (node (ref "R22") (pin "2") (pinfunction "2_2") (pintype "passive"))
    )
    (net (code "20") (name "Net-(Q1-S)") (class "Default")
      (node (ref "C38") (pin "2") (pinfunction "2_2") (pintype "passive"))
      (node (ref "L8") (pin "2") (pinfunction "2_2") (pintype "passive"))
      (node (ref "Q1") (pin "3") (pinfunction "S_3") (pintype "passive"))
      (node (ref "R19") (pin "2") (pinfunction "2_2") (pintype "passive"))
    )
    (net (code "21") (name "Net-(Q2-D)") (class "Default")
      (node (ref "Q2") (pin "3") (pinfunction "D_3") (pintype "passive"))
      (node (ref "R22") (pin "1") (pinfunction "1_1") (pintype "passive"))
    )
    (net (code "22") (name "Net-(Q3-G)") (class "Default")
      (node (ref "C41") (pin "1") (pinfunction "1_1") (pintype "passive"))
      (node (ref "Q3") (pin "4") (pinfunction "G_4") (pintype "passive"))
      (node (ref "U2") (pin "31") (pinfunction "HIDRV1_31") (pintype "output"))
    )
    (net (code "23") (name "Net-(Q3-S1)") (class "Default")
      (node (ref "C69") (pin "1") (pinfunction "1_1") (pintype "passive"))
      (node (ref "L9") (pin "1") (pinfunction "1_1") (pintype "passive"))
      (node (ref "Q3") (pin "1") (pinfunction "S1_1") (pintype "passive"))
      (node (ref "Q3") (pin "2") (pinfunction "S2_2") (pintype "passive"))
      (node (ref "Q3") (pin "3") (pinfunction "S3_3") (pintype "passive"))
      (node (ref "Q4") (pin "5") (pinfunction "D1_5") (pintype "passive"))
      (node (ref "Q4") (pin "6") (pinfunction "D2_6") (pintype "passive"))
      (node (ref "Q4") (pin "7") (pinfunction "D3_7") (pintype "passive"))
      (node (ref "Q4") (pin "8") (pinfunction "D4_8") (pintype "passive"))
      (node (ref "U2") (pin "32") (pinfunction "SW1_32") (pintype "input"))
    )
    (net (code "24") (name "Net-(Q4-G)") (class "Default")
      (node (ref "C42") (pin "1") (pinfunction "1_1") (pintype "passive"))
      (node (ref "Q4") (pin "4") (pinfunction "G_4") (pintype "passive"))
      (node (ref "U2") (pin "29") (pinfunction "LODRV1_29") (pintype "output"))
    )
    (net (code "25") (name "Net-(Q5-G)") (class "Default")
      (node (ref "C61") (pin "1") (pinfunction "1_1") (pintype "passive"))
      (node (ref "Q5") (pin "4") (pinfunction "G_4") (pintype "passive"))
      (node (ref "U2") (pin "24") (pinfunction "HIDRV2_24") (pintype "output"))
    )
    (net (code "26") (name "Net-(Q5-S1)") (class "Default")
      (node (ref "C70") (pin "1") (pinfunction "1_1") (pintype "passive"))
      (node (ref "L9") (pin "2") (pinfunction "2_2") (pintype "passive"))
      (node (ref "Q5") (pin "1") (pinfunction "S1_1") (pintype "passive"))
      (node (ref "Q5") (pin "2") (pinfunction "S2_2") (pintype "passive"))
      (node (ref "Q5") (pin "3") (pinfunction "S3_3") (pintype "passive"))
      (node (ref "Q6") (pin "5") (pinfunction "D1_5") (pintype "passive"))
      (node (ref "Q6") (pin "6") (pinfunction "D2_6") (pintype "passive"))
      (node (ref "Q6") (pin "7") (pinfunction "D3_7") (pintype "passive"))
      (node (ref "Q6") (pin "8") (pinfunction "D4_8") (pintype "passive"))
      (node (ref "U2") (pin "23") (pinfunction "SW2_23") (pintype "input"))
    )
    (net (code "27") (name "Net-(Q6-G)") (class "Default")
      (node (ref "C58") (pin "1") (pinfunction "1_1") (pintype "passive"))
      (node (ref "Q6") (pin "4") (pinfunction "G_4") (pintype "passive"))
      (node (ref "U2") (pin "26") (pinfunction "LODRV2_26") (pintype "output"))
    )
    (net (code "28") (name "Net-(R18-Pad1)") (class "Default")
      (node (ref "R18") (pin "1") (pinfunction "1_1") (pintype "passive"))
      (node (ref "R20") (pin "1") (pinfunction "1_1") (pintype "passive"))
    )
    (net (code "29") (name "Net-(U2-BTST1)") (class "Default")
      (node (ref "C69") (pin "2") (pinfunction "2_2") (pintype "passive"))
      (node (ref "U2") (pin "30") (pinfunction "BTST1_30") (pintype "power_in"))
    )
    (net (code "30") (name "Net-(U2-BTST2)") (class "Default")
      (node (ref "C70") (pin "2") (pinfunction "2_2") (pintype "passive"))
      (node (ref "U2") (pin "25") (pinfunction "BTST2_25") (pintype "power_in"))
    )
    (net (code "31") (name "Net-(U2-CELL_BATPRESZ)") (class "Default")
      (node (ref "R29") (pin "1") (pinfunction "1_1") (pintype "passive"))
      (node (ref "R30") (pin "2") (pinfunction "2_2") (pintype "passive"))
      (node (ref "U2") (pin "18") (pinfunction "CELL_BATPRESZ_18") (pintype "input"))
    )
    (net (code "32") (name "Net-(U2-COMP1)") (class "Default")
      (node (ref "C77") (pin "2") (pinfunction "2_2") (pintype "passive"))
      (node (ref "R38") (pin "2") (pinfunction "2_2") (pintype "passive"))
      (node (ref "U2") (pin "16") (pinfunction "COMP1_16") (pintype "input"))
    )
    (net (code "33") (name "Net-(U2-COMP2)") (class "Default")
      (node (ref "C78") (pin "2") (pinfunction "2_2") (pintype "passive"))
      (node (ref "R37") (pin "2") (pinfunction "2_2") (pintype "passive"))
      (node (ref "U2") (pin "17") (pinfunction "COMP2_17") (pintype "input"))
    )
    (net (code "34") (name "Net-(U2-IADPT)") (class "Default")
      (node (ref "C71") (pin "1") (pinfunction "1_1") (pintype "passive"))
      (node (ref "R33") (pin "2") (pinfunction "2_2") (pintype "passive"))
      (node (ref "U2") (pin "8") (pinfunction "IADPT_8") (pintype "output"))
    )
    (net (code "35") (name "Net-(U2-IBAT)") (class "Default")
      (node (ref "C72") (pin "2") (pinfunction "2_2") (pintype "passive"))
      (node (ref "U2") (pin "9") (pinfunction "IBAT_9") (pintype "output"))
    )
    (net (code "36") (name "Net-(U2-ILIM_HIZ)") (class "Default")
      (node (ref "R31") (pin "1") (pinfunction "1_1") (pintype "passive"))
      (node (ref "R32") (pin "1") (pinfunction "1_1") (pintype "passive"))
      (node (ref "U2") (pin "6") (pinfunction "ILIM_HIZ_6") (pintype "input"))
    )
    (net (code "37") (name "Net-(U2-PSYS)") (class "Default")
      (node (ref "C75") (pin "2") (pinfunction "2_2") (pintype "passive"))
      (node (ref "R36") (pin "2") (pinfunction "2_2") (pintype "passive"))
      (node (ref "U2") (pin "10") (pinfunction "PSYS_10") (pintype "output"))
    )
    (net (code "38") (name "Net-(U2-VBUS)") (class "Default")
      (node (ref "C59") (pin "2") (pinfunction "2_2") (pintype "passive"))
      (node (ref "R24") (pin "1") (pinfunction "1_1") (pintype "passive"))
      (node (ref "U2") (pin "1") (pinfunction "VBUS_1") (pintype "power_in"))
    )
    (net (code "39") (name "VBATT") (class "Default")
      (node (ref "C62") (pin "1") (pinfunction "1_1") (pintype "passive"))
      (node (ref "C66") (pin "1") (pinfunction "1_1") (pintype "passive"))
      (node (ref "C67") (pin "2") (pinfunction "2_2") (pintype "passive"))
      (node (ref "C68") (pin "2") (pinfunction "2_2") (pintype "passive"))
      (node (ref "R28") (pin "1") (pinfunction "1_1") (pintype "passive"))
      (node (ref "R35") (pin "2") (pinfunction "2_2") (pintype "passive"))
      (node (ref "TP9") (pin "1") (pinfunction "1_1") (pintype "passive"))
    )
    (net (code "40") (name "VDDA") (class "Default")
      (node (ref "C63") (pin "2") (pinfunction "2_2") (pintype "passive"))
      (node (ref "R27") (pin "2") (pinfunction "2_2") (pintype "passive"))
      (node (ref "R29") (pin "2") (pinfunction "2_2") (pintype "passive"))
      (node (ref "R31") (pin "2") (pinfunction "2_2") (pintype "passive"))
      (node (ref "U2") (pin "7") (pinfunction "VDDA_7") (pintype "power_in"))
    )
    (net (code "41") (name "VIN") (class "Default")
      (node (ref "C23") (pin "1") (pinfunction "1_1") (pintype "passive"))
      (node (ref "C26") (pin "2") (pinfunction "2_2") (pintype "passive"))
      (node (ref "L7") (pin "1") (pinfunction "1_1") (pintype "passive"))
    )
    (net (code "42") (name "VIN_F") (class "Default")
      (node (ref "C129") (pin "1") (pinfunction "1_1") (pintype "passive"))
      (node (ref "C130") (pin "1") (pinfunction "1_1") (pintype "passive"))
      (node (ref "C24") (pin "1") (pinfunction "1_1") (pintype "passive"))
      (node (ref "C25") (pin "1") (pinfunction "1_1") (pintype "passive"))
      (node (ref "C28") (pin "2") (pinfunction "2_2") (pintype "passive"))
      (node (ref "C29") (pin "2") (pinfunction "2_2") (pintype "passive"))
      (node (ref "C30") (pin "2") (pinfunction "2_2") (pintype "passive"))
      (node (ref "C31") (pin "2") (pinfunction "2_2") (pintype "passive"))
      (node (ref "C32") (pin "2") (pinfunction "2_2") (pintype "passive"))
      (node (ref "C33") (pin "2") (pinfunction "2_2") (pintype "passive"))
      (node (ref "C34") (pin "2") (pinfunction "2_2") (pintype "passive"))
      (node (ref "C35") (pin "2") (pinfunction "2_2") (pintype "passive"))
      (node (ref "C36") (pin "2") (pinfunction "2_2") (pintype "passive"))
      (node (ref "C37") (pin "2") (pinfunction "2_2") (pintype "passive"))
      (node (ref "Q1") (pin "2") (pinfunction "D_2") (pintype "passive"))
      (node (ref "R18") (pin "2") (pinfunction "2_2") (pintype "passive"))
      (node (ref "R23") (pin "1") (pinfunction "1_1") (pintype "passive"))
      (node (ref "R24") (pin "2") (pinfunction "2_2") (pintype "passive"))
      (node (ref "R25") (pin "2") (pinfunction "2_2") (pintype "passive"))
      (node (ref "TP8") (pin "1") (pinfunction "1_1") (pintype "passive"))
    )
    (net (code "43") (name "VREGN") (class "Default")
      (node (ref "C43") (pin "2") (pinfunction "2_2") (pintype "passive"))
      (node (ref "C44") (pin "2") (pinfunction "2_2") (pintype "passive"))
      (node (ref "C45") (pin "2") (pinfunction "2_2") (pintype "passive"))
      (node (ref "R27") (pin "1") (pinfunction "1_1") (pintype "passive"))
      (node (ref "U2") (pin "28") (pinfunction "REGN_28") (pintype "power_in"))
    )
    (net (code "44") (name "VSYS") (class "Default")
      (node (ref "C46") (pin "2") (pinfunction "2_2") (pintype "passive"))
      (node (ref "C47") (pin "2") (pinfunction "2_2") (pintype "passive"))
      (node (ref "C48") (pin "2") (pinfunction "2_2") (pintype "passive"))
      (node (ref "C49") (pin "2") (pinfunction "2_2") (pintype "passive"))
      (node (ref "C50") (pin "2") (pinfunction "2_2") (pintype "passive"))
      (node (ref "C51") (pin "2") (pinfunction "2_2") (pintype "passive"))
      (node (ref "C52") (pin "2") (pinfunction "2_2") (pintype "passive"))
      (node (ref "C53") (pin "2") (pinfunction "2_2") (pintype "passive"))
      (node (ref "C54") (pin "2") (pinfunction "2_2") (pintype "passive"))
      (node (ref "C55") (pin "2") (pinfunction "2_2") (pintype "passive"))
      (node (ref "C56") (pin "2") (pinfunction "2_2") (pintype "passive"))
      (node (ref "C57") (pin "2") (pinfunction "2_2") (pintype "passive"))
      (node (ref "C62") (pin "2") (pinfunction "2_2") (pintype "passive"))
      (node (ref "Q5") (pin "5") (pinfunction "D1_5") (pintype "passive"))
      (node (ref "Q5") (pin "6") (pinfunction "D2_6") (pintype "passive"))
      (node (ref "Q5") (pin "7") (pinfunction "D3_7") (pintype "passive"))
      (node (ref "Q5") (pin "8") (pinfunction "D4_8") (pintype "passive"))
      (node (ref "R28") (pin "2") (pinfunction "2_2") (pintype "passive"))
      (node (ref "R34") (pin "2") (pinfunction "2_2") (pintype "passive"))
      (node (ref "TP1") (pin "1") (pinfunction "1_1") (pintype "passive"))
      (node (ref "U2") (pin "22") (pinfunction "VSYS_22") (pintype "input"))
    )
    (net (code "45") (name "unconnected-(U2-~{BATDRV}{slash}NC-Pad21)") (class "Default")
      (node (ref "U2") (pin "21") (pinfunction "~{BATDRV}/NC_21") (pintype "open_collector"))
    )
  )
)
